# max30105_breakout.net
KiCad netlist of a schematic drawn in EAGLE
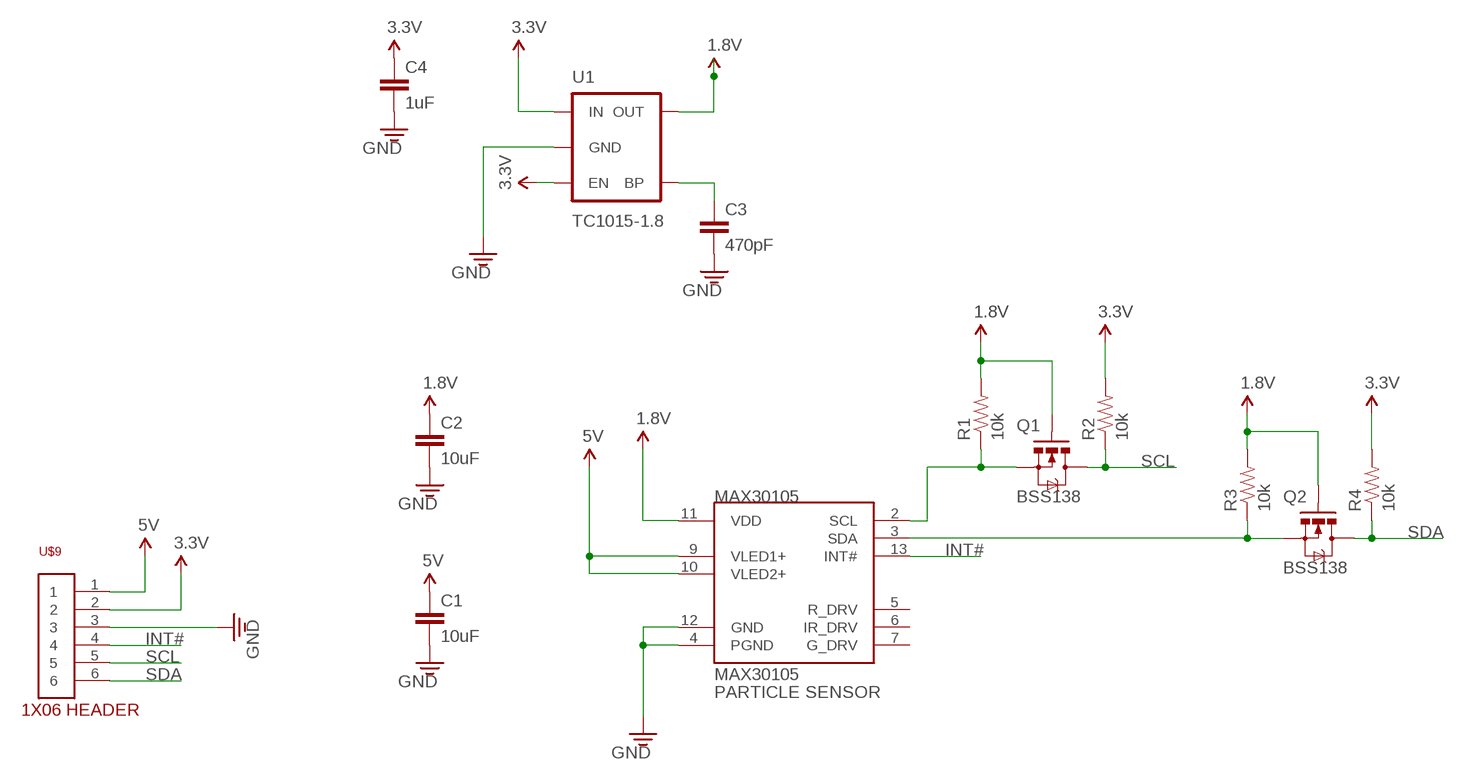
[diagram p0: schematic, sheet 1]

(export (version "E")
  (design (tool "Eeschema 10.0.6"))
  (components
    (comp (ref "C1")
      (value "10uF")
      (footprint "eagle-import:0805")
      (libsource (lib "eagle-import") (part "CAP0805"))
    )
    (comp (ref "C2")
      (value "10uF")
      (footprint "eagle-import:0805")
      (libsource (lib "eagle-import") (part "CAP0805"))
    )
    (comp (ref "C3")
      (value "470pF")
      (footprint "eagle-import:0603")
      (libsource (lib "eagle-import") (part "CAP0603"))
    )
    (comp (ref "C4")
      (value "1uF")
      (footprint "eagle-import:0603")
      (libsource (lib "eagle-import") (part "CAP0603"))
    )
    (comp (ref "MAX30105")
      (value "MAX30105")
      (footprint "eagle-import:MAX30105")
      (libsource (lib "eagle-import") (part "MAX30105"))
    )
    (comp (ref "Q1")
      (value "BSS138")
      (footprint "eagle-import:SOT23")
      (libsource (lib "eagle-import") (part "MOSFET-NCHANNELBSS138"))
    )
    (comp (ref "Q2")
      (value "BSS138")
      (footprint "eagle-import:SOT23")
      (libsource (lib "eagle-import") (part "MOSFET-NCHANNELBSS138"))
    )
    (comp (ref "R1")
      (value "10k")
      (footprint "eagle-import:0603")
      (libsource (lib "eagle-import") (part "RESISTOR0603"))
    )
    (comp (ref "R2")
      (value "10k")
      (footprint "eagle-import:0603")
      (libsource (lib "eagle-import") (part "RESISTOR0603"))
    )
    (comp (ref "R3")
      (value "10k")
      (footprint "eagle-import:0603")
      (libsource (lib "eagle-import") (part "RESISTOR0603"))
    )
    (comp (ref "R4")
      (value "10k")
      (footprint "eagle-import:0603")
      (libsource (lib "eagle-import") (part "RESISTOR0603"))
    )
    (comp (ref "U$9")
      (value "1X06")
      (footprint "eagle-import:1X06")
      (libsource (lib "eagle-import") (part "1X06"))
    )
    (comp (ref "U1")
      (value "TC1015-1.8")
      (footprint "eagle-import:SOT23-5")
      (libsource (lib "eagle-import") (part "V_REG_LDOSMD"))
    )
  )
  (nets
    (net (code "1") (name "/INT#") (class "Default")
      (node (ref "MAX30105") (pin "13") (pinfunction "INT#_13") (pintype "bidirectional"))
      (node (ref "U$9") (pin "4") (pinfunction "4_4") (pintype "bidirectional"))
    )
    (net (code "2") (name "/SCL") (class "Default")
      (node (ref "Q1") (pin "3") (pinfunction "D_3") (pintype "passive"))
      (node (ref "R2") (pin "1") (pinfunction "1_1") (pintype "passive"))
      (node (ref "U$9") (pin "5") (pinfunction "5_5") (pintype "bidirectional"))
    )
    (net (code "3") (name "/SDA") (class "Default")
      (node (ref "Q2") (pin "3") (pinfunction "D_3") (pintype "passive"))
      (node (ref "R4") (pin "1") (pinfunction "1_1") (pintype "passive"))
      (node (ref "U$9") (pin "6") (pinfunction "6_6") (pintype "bidirectional"))
    )
    (net (code "4") (name "1.8V") (class "Default")
      (node (ref "C2") (pin "1") (pinfunction "1_1") (pintype "passive"))
      (node (ref "MAX30105") (pin "11") (pinfunction "VDD_11") (pintype "bidirectional"))
      (node (ref "Q1") (pin "1") (pinfunction "G_1") (pintype "passive"))
      (node (ref "Q2") (pin "1") (pinfunction "G_1") (pintype "passive"))
      (node (ref "R1") (pin "2") (pinfunction "2_2") (pintype "passive"))
      (node (ref "R3") (pin "2") (pinfunction "2_2") (pintype "passive"))
      (node (ref "U1") (pin "5") (pinfunction "OUT_5") (pintype "passive"))
    )
    (net (code "5") (name "3.3V") (class "Default")
      (node (ref "C4") (pin "1") (pinfunction "1_1") (pintype "passive"))
      (node (ref "R2") (pin "2") (pinfunction "2_2") (pintype "passive"))
      (node (ref "R4") (pin "2") (pinfunction "2_2") (pintype "passive"))
      (node (ref "U$9") (pin "2") (pinfunction "2_2") (pintype "bidirectional"))
      (node (ref "U1") (pin "1") (pinfunction "IN_1") (pintype "input"))
      (node (ref "U1") (pin "3") (pinfunction "EN_3") (pintype "input"))
    )
    (net (code "6") (name "5V") (class "Default")
      (node (ref "C1") (pin "1") (pinfunction "1_1") (pintype "passive"))
      (node (ref "MAX30105") (pin "10") (pinfunction "VLED2+_10") (pintype "bidirectional"))
      (node (ref "MAX30105") (pin "9") (pinfunction "VLED1+_9") (pintype "bidirectional"))
      (node (ref "U$9") (pin "1") (pinfunction "1_1") (pintype "bidirectional"))
    )
    (net (code "7") (name "GND") (class "Default")
      (node (ref "C1") (pin "2") (pinfunction "2_2") (pintype "passive"))
      (node (ref "C2") (pin "2") (pinfunction "2_2") (pintype "passive"))
      (node (ref "C3") (pin "2") (pinfunction "2_2") (pintype "passive"))
      (node (ref "C4") (pin "2") (pinfunction "2_2") (pintype "passive"))
      (node (ref "MAX30105") (pin "12") (pinfunction "GND_12") (pintype "bidirectional"))
      (node (ref "MAX30105") (pin "4") (pinfunction "PGND_4") (pintype "bidirectional"))
      (node (ref "U$9") (pin "3") (pinfunction "3_3") (pintype "bidirectional"))
      (node (ref "U1") (pin "2") (pinfunction "GND_2") (pintype "input"))
    )
    (net (code "8") (name "Net-(MAX30105-SCL)") (class "Default")
      (node (ref "MAX30105") (pin "2") (pinfunction "SCL_2") (pintype "bidirectional"))
      (node (ref "Q1") (pin "2") (pinfunction "S_2") (pintype "passive"))
      (node (ref "R1") (pin "1") (pinfunction "1_1") (pintype "passive"))
    )
    (net (code "9") (name "Net-(MAX30105-SDA)") (class "Default")
      (node (ref "MAX30105") (pin "3") (pinfunction "SDA_3") (pintype "bidirectional"))
      (node (ref "Q2") (pin "2") (pinfunction "S_2") (pintype "passive"))
      (node (ref "R3") (pin "1") (pinfunction "1_1") (pintype "passive"))
    )
    (net (code "10") (name "Net-(U1-BP)") (class "Default")
      (node (ref "C3") (pin "1") (pinfunction "1_1") (pintype "passive"))
      (node (ref "U1") (pin "4") (pinfunction "BP_4") (pintype "input"))
    )
    (net (code "11") (name "unconnected-(MAX30105-G_DRV-Pad7)") (class "Default")
      (node (ref "MAX30105") (pin "7") (pinfunction "G_DRV_7") (pintype "bidirectional"))
    )
    (net (code "12") (name "unconnected-(MAX30105-IR_DRV-Pad6)") (class "Default")
      (node (ref "MAX30105") (pin "6") (pinfunction "IR_DRV_6") (pintype "bidirectional"))
    )
    (net (code "13") (name "unconnected-(MAX30105-R_DRV-Pad5)") (class "Default")
      (node (ref "MAX30105") (pin "5") (pinfunction "R_DRV_5") (pintype "bidirectional"))
    )
  )
)
